# untitled.net
KiCad netlist of a schematic drawn in EAGLE
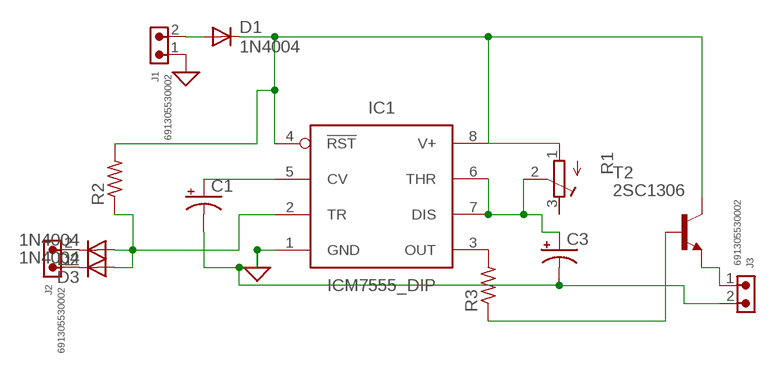
[diagram p0: schematic, sheet 1]

(export (version "E")
  (design (tool "Eeschema 10.0.6"))
  (components
    (comp (ref "C1")
      (value "CAPACITOR-PE2.5-5")
      (footprint "eagle-import:E2,5-5")
      (libsource (lib "eagle-import") (part "CAPACITOR-PE2.5-5"))
    )
    (comp (ref "C3")
      (value "CAPACITOR-PE2.5-5")
      (footprint "eagle-import:E2,5-5")
      (libsource (lib "eagle-import") (part "CAPACITOR-PE2.5-5"))
    )
    (comp (ref "D1")
      (value "1N4004")
      (footprint "eagle-import:DO41-10")
      (libsource (lib "eagle-import") (part "1N4004"))
    )
    (comp (ref "D2")
      (value "1N4004")
      (footprint "eagle-import:DO41-10")
      (libsource (lib "eagle-import") (part "1N4004"))
    )
    (comp (ref "D3")
      (value "1N4004")
      (footprint "eagle-import:DO41-10")
      (libsource (lib "eagle-import") (part "1N4004"))
    )
    (comp (ref "IC1")
      (value "ICM7555_DIP")
      (footprint "eagle-import:DIP826W53P254L959H508Q8B")
      (fields
        (field (name "MANUFACTURER") "Renesas Electronics America Inc ")
        (field (name "MPN") "ICM7555IPAZ ")
      )
      (libsource (lib "eagle-import") (part "555_DIPICM7"))
    )
    (comp (ref "J1")
      (value "691305530002")
      (footprint "eagle-import:691305530002")
      (libsource (lib "eagle-import") (part "691305530002"))
    )
    (comp (ref "J2")
      (value "691305530002")
      (footprint "eagle-import:691305530002")
      (libsource (lib "eagle-import") (part "691305530002"))
    )
    (comp (ref "J3")
      (value "691305530002")
      (footprint "eagle-import:691305530002")
      (libsource (lib "eagle-import") (part "691305530002"))
    )
    (comp (ref "R1")
      (value "R-TRIMM3296X")
      (footprint "eagle-import:RTRIM3296X")
      (libsource (lib "eagle-import") (part "R-TRIMM3296X"))
    )
    (comp (ref "R2")
      (value "R-US_0207/7")
      (footprint "eagle-import:0207_7")
      (libsource (lib "eagle-import") (part "R-US_0207/7"))
    )
    (comp (ref "R3")
      (value "R-US_0207/7")
      (footprint "eagle-import:0207_7")
      (libsource (lib "eagle-import") (part "R-US_0207/7"))
    )
    (comp (ref "T2")
      (value "2SC1306")
      (footprint "eagle-import:TO220BV")
      (libsource (lib "eagle-import") (part "2SC1306"))
    )
  )
  (nets
    (net (code "1") (name "Net-(D1-PadA)") (class "Default")
      (node (ref "D1") (pin "A") (pinfunction "A_A") (pintype "passive"))
      (node (ref "J1") (pin "2") (pinfunction "2_2") (pintype "passive"))
    )
    (net (code "2") (name "Net-(D2-PadC)") (class "Default")
      (node (ref "D2") (pin "C") (pinfunction "C_C") (pintype "passive"))
      (node (ref "J2") (pin "2") (pinfunction "2_2") (pintype "passive"))
    )
    (net (code "3") (name "Net-(D3-PadC)") (class "Default")
      (node (ref "D3") (pin "C") (pinfunction "C_C") (pintype "passive"))
      (node (ref "J2") (pin "1") (pinfunction "1_1") (pintype "passive"))
    )
    (net (code "4") (name "Net-(IC1-CV)") (class "Default")
      (node (ref "C1") (pin "+") (pinfunction "+_+") (pintype "passive"))
      (node (ref "IC1") (pin "5") (pinfunction "CV_5") (pintype "input"))
    )
    (net (code "5") (name "Net-(IC1-DIS)") (class "Default")
      (node (ref "C3") (pin "+") (pinfunction "+_+") (pintype "passive"))
      (node (ref "IC1") (pin "6") (pinfunction "THR_6") (pintype "input"))
      (node (ref "IC1") (pin "7") (pinfunction "DIS_7") (pintype "input"))
      (node (ref "R1") (pin "2") (pinfunction "S_2") (pintype "passive"))
    )
    (net (code "6") (name "Net-(IC1-OUT)") (class "Default")
      (node (ref "IC1") (pin "3") (pinfunction "OUT_3") (pintype "output"))
      (node (ref "R3") (pin "2") (pinfunction "2_2") (pintype "passive"))
    )
    (net (code "7") (name "Net-(IC1-TR)") (class "Default")
      (node (ref "D2") (pin "A") (pinfunction "A_A") (pintype "passive"))
      (node (ref "D3") (pin "A") (pinfunction "A_A") (pintype "passive"))
      (node (ref "IC1") (pin "2") (pinfunction "TR_2") (pintype "input"))
      (node (ref "R2") (pin "1") (pinfunction "1_1") (pintype "passive"))
    )
    (net (code "8") (name "Net-(IC1-V+)") (class "Default")
      (node (ref "D1") (pin "C") (pinfunction "C_C") (pintype "passive"))
      (node (ref "IC1") (pin "4") (pinfunction "~{RST}_4") (pintype "input"))
      (node (ref "IC1") (pin "8") (pinfunction "V+_8") (pintype "power_in"))
      (node (ref "R1") (pin "1") (pinfunction "A_1") (pintype "passive"))
      (node (ref "R2") (pin "2") (pinfunction "2_2") (pintype "passive"))
      (node (ref "T2") (pin "2") (pinfunction "C_2") (pintype "passive"))
    )
    (net (code "9") (name "Net-(T2-B)") (class "Default")
      (node (ref "R3") (pin "1") (pinfunction "1_1") (pintype "passive"))
      (node (ref "T2") (pin "1") (pinfunction "B_1") (pintype "passive"))
    )
    (net (code "10") (name "Net-(T2-E)") (class "Default")
      (node (ref "J3") (pin "1") (pinfunction "1_1") (pintype "passive"))
      (node (ref "T2") (pin "3") (pinfunction "E_3") (pintype "passive"))
    )
    (net (code "11") (name "SUP") (class "Default")
      (node (ref "C1") (pin "-") (pinfunction "-_-") (pintype "passive"))
      (node (ref "C3") (pin "-") (pinfunction "-_-") (pintype "passive"))
      (node (ref "IC1") (pin "1") (pinfunction "GND_1") (pintype "power_in"))
      (node (ref "J1") (pin "1") (pinfunction "1_1") (pintype "passive"))
      (node (ref "J3") (pin "2") (pinfunction "2_2") (pintype "passive"))
    )
    (net (code "12") (name "unconnected-(R1-E-Pad3)") (class "Default")
      (node (ref "R1") (pin "3") (pinfunction "E_3") (pintype "passive"))
    )
  )
)
